# RH025_V2_1.net
KiCad netlist of a schematic drawn in EAGLE
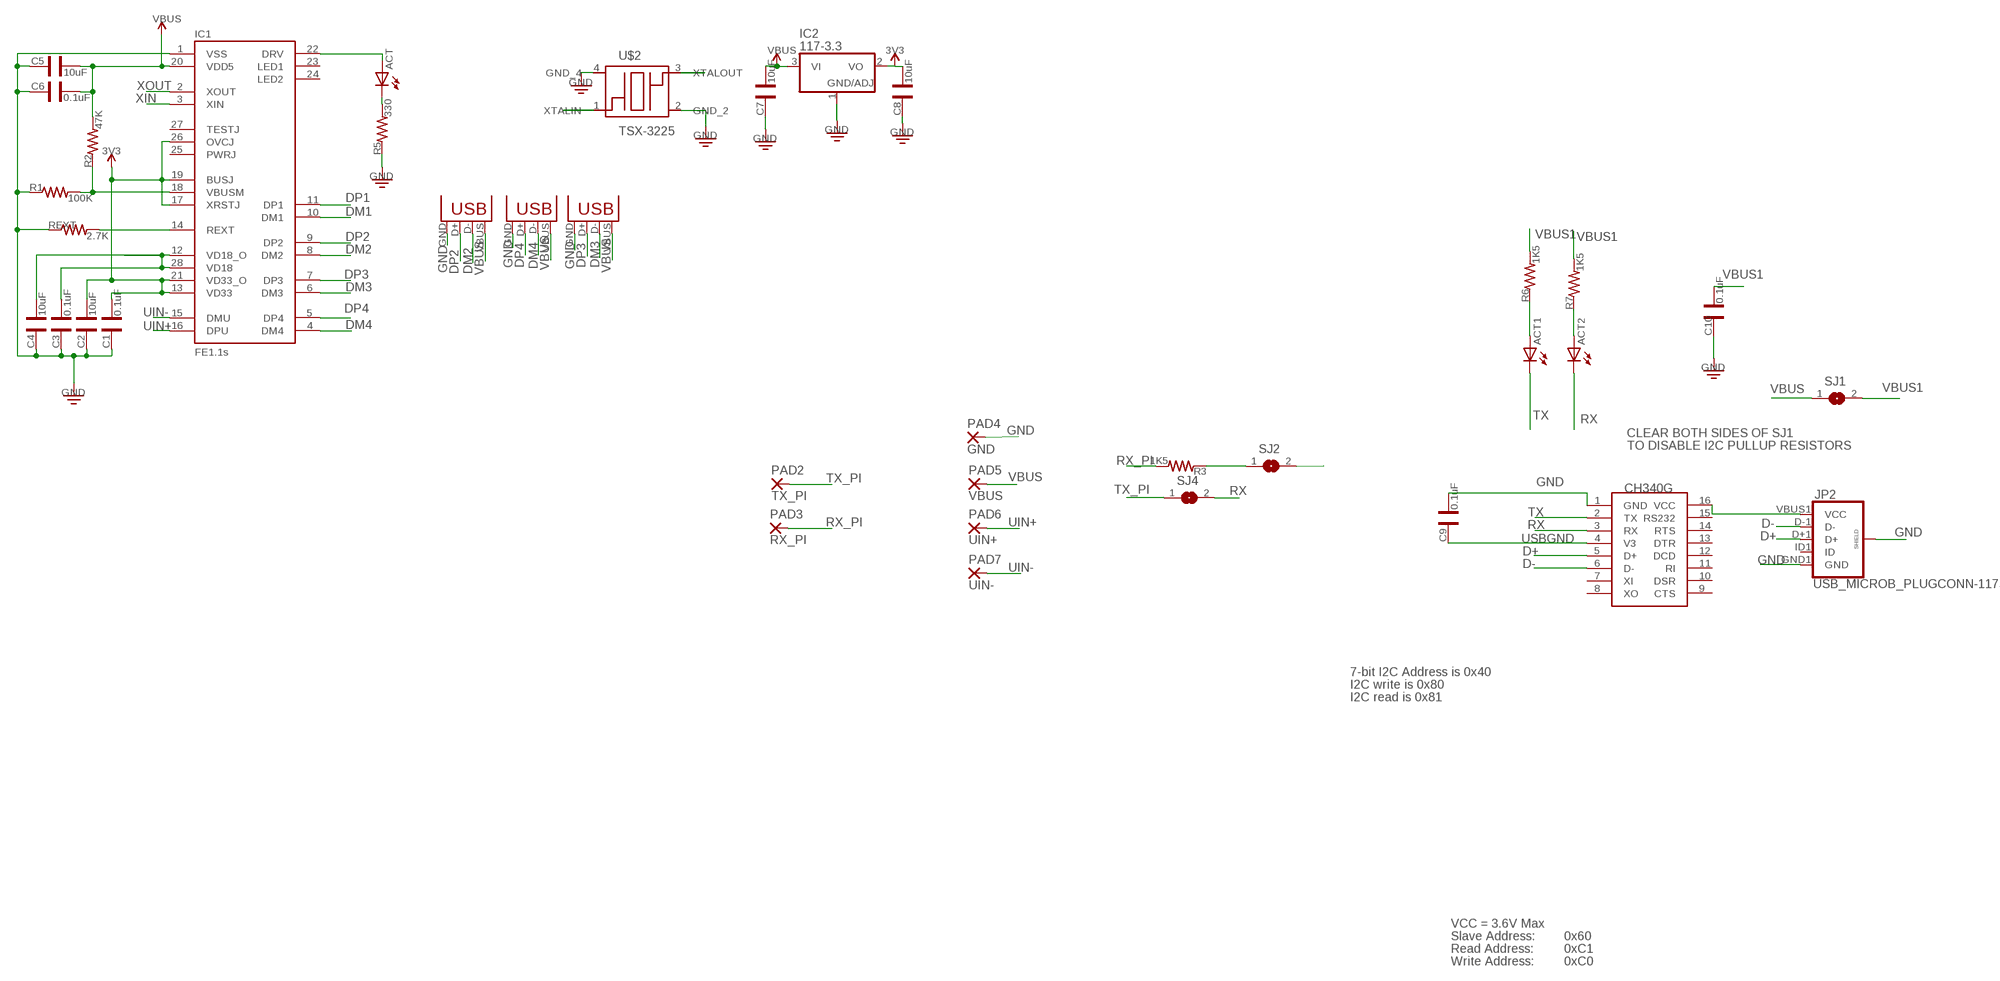
[diagram p0: schematic, sheet 1]

(export (version "E")
  (design (tool "Eeschema 10.0.6"))
  (components
    (comp (ref "ACT")
      (value "LED0805")
      (footprint "eagle-import:LED-0805")
      (libsource (lib "eagle-import") (part "LED0805"))
    )
    (comp (ref "ACT1")
      (value "LED0805")
      (footprint "eagle-import:LED-0805")
      (libsource (lib "eagle-import") (part "LED0805"))
    )
    (comp (ref "ACT2")
      (value "LED0805")
      (footprint "eagle-import:LED-0805")
      (libsource (lib "eagle-import") (part "LED0805"))
    )
    (comp (ref "C1")
      (value "0.1uF")
      (footprint "eagle-import:CAP-0805")
      (libsource (lib "eagle-import") (part "CAP0805"))
    )
    (comp (ref "C2")
      (value "10uF")
      (footprint "eagle-import:CAP-0805")
      (libsource (lib "eagle-import") (part "CAP0805"))
    )
    (comp (ref "C3")
      (value "0.1uF")
      (footprint "eagle-import:CAP-0805")
      (libsource (lib "eagle-import") (part "CAP0805"))
    )
    (comp (ref "C4")
      (value "10uF")
      (footprint "eagle-import:CAP-0805")
      (libsource (lib "eagle-import") (part "CAP0805"))
    )
    (comp (ref "C5")
      (value "10uF")
      (footprint "eagle-import:CAP-0805")
      (libsource (lib "eagle-import") (part "CAP0805"))
    )
    (comp (ref "C6")
      (value "0.1uF")
      (footprint "eagle-import:CAP-0805")
      (libsource (lib "eagle-import") (part "CAP0805"))
    )
    (comp (ref "C7")
      (value "10uF")
      (footprint "eagle-import:CAP-0805")
      (libsource (lib "eagle-import") (part "CAP0805"))
    )
    (comp (ref "C8")
      (value "10uF")
      (footprint "eagle-import:CAP-0805")
      (libsource (lib "eagle-import") (part "CAP0805"))
    )
    (comp (ref "C9")
      (value "0.1uF")
      (footprint "eagle-import:CAP-0805")
      (libsource (lib "eagle-import") (part "CAP0805"))
    )
    (comp (ref "C10")
      (value "0.1uF")
      (footprint "eagle-import:CAP-0805")
      (libsource (lib "eagle-import") (part "CAP0805"))
    )
    (comp (ref "IC1")
      (value "FE1.1S")
      (footprint "eagle-import:FE1.1S_SSOP-28")
      (libsource (lib "eagle-import") (part "FE1.1S"))
    )
    (comp (ref "IC2")
      (value "117-3.3")
      (footprint "eagle-import:SOT223")
      (libsource (lib "eagle-import") (part "1117-3.3EMP"))
    )
    (comp (ref "JP2")
      (value "USB_MICROB_PLUGCONN-11752")
      (footprint "eagle-import:USB-B-MICRO-SMD_V03")
      (libsource (lib "eagle-import") (part "USB_MICROB_PLUGCONN-11752"))
    )
    (comp (ref "PAD2")
      (value "TX_PI")
      (footprint "eagle-import:2,15_1,0")
      (libsource (lib "eagle-import") (part "WIREPAD2,15/1,0"))
    )
    (comp (ref "PAD3")
      (value "RX_PI")
      (footprint "eagle-import:2,15_1,0")
      (libsource (lib "eagle-import") (part "WIREPAD2,15/1,0"))
    )
    (comp (ref "PAD4")
      (value "GND")
      (footprint "eagle-import:2,15_1,0")
      (libsource (lib "eagle-import") (part "WIREPAD2,15/1,0"))
    )
    (comp (ref "PAD5")
      (value "VBUS")
      (footprint "eagle-import:2,15_1,0")
      (libsource (lib "eagle-import") (part "WIREPAD2,15/1,0"))
    )
    (comp (ref "PAD6")
      (value "UIN+")
      (footprint "eagle-import:2,15_1,0")
      (libsource (lib "eagle-import") (part "WIREPAD2,15/1,0"))
    )
    (comp (ref "PAD7")
      (value "UIN-")
      (footprint "eagle-import:2,15_1,0")
      (libsource (lib "eagle-import") (part "WIREPAD2,15/1,0"))
    )
    (comp (ref "R1")
      (value "100K")
      (footprint "eagle-import:RES-0805")
      (libsource (lib "eagle-import") (part "RES0805"))
    )
    (comp (ref "R2")
      (value "47K")
      (footprint "eagle-import:RES-0805")
      (libsource (lib "eagle-import") (part "RES0805"))
    )
    (comp (ref "R3")
      (value "1K5")
      (footprint "eagle-import:RES-0805")
      (libsource (lib "eagle-import") (part "RES0805"))
    )
    (comp (ref "R5")
      (value "330")
      (footprint "eagle-import:RES-0805")
      (libsource (lib "eagle-import") (part "RES0805"))
    )
    (comp (ref "R6")
      (value "1K5")
      (footprint "eagle-import:RES-0805")
      (libsource (lib "eagle-import") (part "RES0805"))
    )
    (comp (ref "R7")
      (value "1K5")
      (footprint "eagle-import:RES-0805")
      (libsource (lib "eagle-import") (part "RES0805"))
    )
    (comp (ref "REXT")
      (value "2.7K")
      (footprint "eagle-import:RES-0805")
      (libsource (lib "eagle-import") (part "RES0805"))
    )
    (comp (ref "SJ1") (value "SJ") (footprint "eagle-import:SJ") (libsource (lib "eagle-import") (part "SJ")))
    (comp (ref "SJ2") (value "SJ") (footprint "eagle-import:SJ") (libsource (lib "eagle-import") (part "SJ")))
    (comp (ref "SJ4") (value "SJ") (footprint "eagle-import:SJ") (libsource (lib "eagle-import") (part "SJ")))
    (comp (ref "U$2")
      (value "TSX-3225")
      (footprint "eagle-import:TSX-3225")
      (libsource (lib "eagle-import") (part "TSX-3225"))
    )
    (comp (ref "U$8")
      (value "CH340C")
      (footprint "eagle-import:SOIC16")
      (libsource (lib "eagle-import") (part "CH340G"))
    )
    (comp (ref "USB2")
      (value "USBA-PTH")
      (footprint "eagle-import:USB-A-F-PTH")
      (libsource (lib "eagle-import") (part "USBA-PTH"))
    )
    (comp (ref "USB3")
      (value "USBA-PTH")
      (footprint "eagle-import:USB-A-F-PTH")
      (libsource (lib "eagle-import") (part "USBA-PTH"))
    )
    (comp (ref "USB4")
      (value "USBA-PTH")
      (footprint "eagle-import:USB-A-F-PTH")
      (libsource (lib "eagle-import") (part "USBA-PTH"))
    )
  )
  (nets
    (net (code "1") (name "/D+") (class "Default")
      (node (ref "JP2") (pin "D+1") (pinfunction "D+_D+1") (pintype "bidirectional"))
      (node (ref "U$8") (pin "5") (pinfunction "D+_5") (pintype "bidirectional"))
    )
    (net (code "2") (name "/D-") (class "Default")
      (node (ref "JP2") (pin "D-1") (pinfunction "D-_D-1") (pintype "bidirectional"))
      (node (ref "U$8") (pin "6") (pinfunction "D-_6") (pintype "bidirectional"))
    )
    (net (code "3") (name "/DM1") (class "Default")
      (node (ref "IC1") (pin "10") (pinfunction "DM1_10") (pintype "bidirectional"))
    )
    (net (code "4") (name "/DM2") (class "Default")
      (node (ref "IC1") (pin "8") (pinfunction "DM2_8") (pintype "bidirectional"))
      (node (ref "USB2") (pin "D-") (pinfunction "D-_D-") (pintype "bidirectional"))
    )
    (net (code "5") (name "/DM3") (class "Default")
      (node (ref "IC1") (pin "6") (pinfunction "DM3_6") (pintype "bidirectional"))
      (node (ref "USB3") (pin "D-") (pinfunction "D-_D-") (pintype "bidirectional"))
    )
    (net (code "6") (name "/DM4") (class "Default")
      (node (ref "IC1") (pin "4") (pinfunction "DM4_4") (pintype "bidirectional"))
      (node (ref "USB4") (pin "D-") (pinfunction "D-_D-") (pintype "bidirectional"))
    )
    (net (code "7") (name "/DP1") (class "Default")
      (node (ref "IC1") (pin "11") (pinfunction "DP1_11") (pintype "bidirectional"))
    )
    (net (code "8") (name "/DP2") (class "Default")
      (node (ref "IC1") (pin "9") (pinfunction "DP2_9") (pintype "bidirectional"))
      (node (ref "USB2") (pin "D+") (pinfunction "D+_D+") (pintype "bidirectional"))
    )
    (net (code "9") (name "/DP3") (class "Default")
      (node (ref "IC1") (pin "7") (pinfunction "DP3_7") (pintype "bidirectional"))
      (node (ref "USB3") (pin "D+") (pinfunction "D+_D+") (pintype "bidirectional"))
    )
    (net (code "10") (name "/DP4") (class "Default")
      (node (ref "IC1") (pin "5") (pinfunction "DP4_5") (pintype "bidirectional"))
      (node (ref "USB4") (pin "D+") (pinfunction "D+_D+") (pintype "bidirectional"))
    )
    (net (code "11") (name "/RX") (class "Default")
      (node (ref "ACT2") (pin "C") (pinfunction "C_C") (pintype "passive"))
      (node (ref "SJ4") (pin "2") (pinfunction "2_2") (pintype "passive"))
      (node (ref "U$8") (pin "3") (pinfunction "RX_3") (pintype "bidirectional"))
    )
    (net (code "12") (name "/RX_PI") (class "Default")
      (node (ref "PAD3") (pin "1") (pinfunction "P_1") (pintype "passive"))
      (node (ref "R3") (pin "2") (pinfunction "2_2") (pintype "passive"))
    )
    (net (code "13") (name "/TX") (class "Default")
      (node (ref "ACT1") (pin "C") (pinfunction "C_C") (pintype "passive"))
      (node (ref "SJ2") (pin "2") (pinfunction "2_2") (pintype "passive"))
      (node (ref "U$8") (pin "2") (pinfunction "TX_2") (pintype "bidirectional"))
    )
    (net (code "14") (name "/TX_PI") (class "Default")
      (node (ref "PAD2") (pin "1") (pinfunction "P_1") (pintype "passive"))
      (node (ref "SJ4") (pin "1") (pinfunction "1_1") (pintype "passive"))
    )
    (net (code "15") (name "/UIN+") (class "Default")
      (node (ref "IC1") (pin "16") (pinfunction "DPU_16") (pintype "bidirectional"))
      (node (ref "PAD6") (pin "1") (pinfunction "P_1") (pintype "passive"))
    )
    (net (code "16") (name "/UIN-") (class "Default")
      (node (ref "IC1") (pin "15") (pinfunction "DMU_15") (pintype "bidirectional"))
      (node (ref "PAD7") (pin "1") (pinfunction "P_1") (pintype "passive"))
    )
    (net (code "17") (name "/USBGND") (class "Default")
      (node (ref "C9") (pin "2") (pinfunction "2_2") (pintype "passive"))
      (node (ref "U$8") (pin "4") (pinfunction "V3_4") (pintype "bidirectional"))
    )
    (net (code "18") (name "/VBUS1") (class "Default")
      (node (ref "C10") (pin "1") (pinfunction "1_1") (pintype "passive"))
      (node (ref "JP2") (pin "VBUS1") (pinfunction "VCC_VBUS1") (pintype "bidirectional"))
      (node (ref "R6") (pin "2") (pinfunction "2_2") (pintype "passive"))
      (node (ref "R7") (pin "2") (pinfunction "2_2") (pintype "passive"))
      (node (ref "SJ1") (pin "2") (pinfunction "2_2") (pintype "passive"))
      (node (ref "U$8") (pin "16") (pinfunction "VCC_16") (pintype "bidirectional"))
    )
    (net (code "19") (name "/XIN") (class "Default")
      (node (ref "IC1") (pin "3") (pinfunction "XIN_3") (pintype "bidirectional"))
      (node (ref "U$2") (pin "1") (pinfunction "XTALIN_1") (pintype "bidirectional"))
    )
    (net (code "20") (name "/XOUT") (class "Default")
      (node (ref "IC1") (pin "2") (pinfunction "XOUT_2") (pintype "bidirectional"))
      (node (ref "U$2") (pin "3") (pinfunction "XTALOUT_3") (pintype "bidirectional"))
    )
    (net (code "21") (name "3V3") (class "Default")
      (node (ref "C1") (pin "1") (pinfunction "1_1") (pintype "passive"))
      (node (ref "C2") (pin "1") (pinfunction "1_1") (pintype "passive"))
      (node (ref "C8") (pin "1") (pinfunction "1_1") (pintype "passive"))
      (node (ref "IC1") (pin "13") (pinfunction "VD33_13") (pintype "bidirectional"))
      (node (ref "IC1") (pin "17") (pinfunction "XRSTJ_17") (pintype "bidirectional"))
      (node (ref "IC1") (pin "19") (pinfunction "BUSJ_19") (pintype "bidirectional"))
      (node (ref "IC1") (pin "21") (pinfunction "VD33_O_21") (pintype "bidirectional"))
      (node (ref "IC1") (pin "26") (pinfunction "OVCJ_26") (pintype "bidirectional"))
      (node (ref "IC2") (pin "2") (pinfunction "VO_2") (pintype "output"))
    )
    (net (code "22") (name "GND") (class "Default")
      (node (ref "C1") (pin "2") (pinfunction "2_2") (pintype "passive"))
      (node (ref "C10") (pin "2") (pinfunction "2_2") (pintype "passive"))
      (node (ref "C2") (pin "2") (pinfunction "2_2") (pintype "passive"))
      (node (ref "C3") (pin "2") (pinfunction "2_2") (pintype "passive"))
      (node (ref "C4") (pin "2") (pinfunction "2_2") (pintype "passive"))
      (node (ref "C5") (pin "2") (pinfunction "2_2") (pintype "passive"))
      (node (ref "C6") (pin "2") (pinfunction "2_2") (pintype "passive"))
      (node (ref "C7") (pin "2") (pinfunction "2_2") (pintype "passive"))
      (node (ref "C8") (pin "2") (pinfunction "2_2") (pintype "passive"))
      (node (ref "C9") (pin "1") (pinfunction "1_1") (pintype "passive"))
      (node (ref "IC1") (pin "1") (pinfunction "VSS_1") (pintype "bidirectional"))
      (node (ref "IC2") (pin "1") (pinfunction "ADJ_1") (pintype "input"))
      (node (ref "JP2") (pin "GND1") (pinfunction "GND_GND1") (pintype "bidirectional"))
      (node (ref "JP2") (pin "SHIELD1") (pinfunction "SHIELD_SHIELD1") (pintype "bidirectional"))
      (node (ref "JP2") (pin "SHIELD2") (pinfunction "SHIELD_SHIELD2") (pintype "bidirectional"))
      (node (ref "JP2") (pin "SHIELD3") (pinfunction "SHIELD_SHIELD3") (pintype "bidirectional"))
      (node (ref "PAD4") (pin "1") (pinfunction "P_1") (pintype "passive"))
      (node (ref "R1") (pin "1") (pinfunction "1_1") (pintype "passive"))
      (node (ref "R5") (pin "1") (pinfunction "1_1") (pintype "passive"))
      (node (ref "REXT") (pin "1") (pinfunction "1_1") (pintype "passive"))
      (node (ref "U$2") (pin "2") (pinfunction "GND_2_2") (pintype "bidirectional"))
      (node (ref "U$2") (pin "4") (pinfunction "GND_4_4") (pintype "bidirectional"))
      (node (ref "U$8") (pin "1") (pinfunction "GND_1") (pintype "bidirectional"))
      (node (ref "USB2") (pin "GND") (pinfunction "GND_GND") (pintype "bidirectional"))
      (node (ref "USB3") (pin "GND") (pinfunction "GND_GND") (pintype "bidirectional"))
      (node (ref "USB4") (pin "GND") (pinfunction "GND_GND") (pintype "bidirectional"))
    )
    (net (code "23") (name "Net-(ACT-PadC)") (class "Default")
      (node (ref "ACT") (pin "C") (pinfunction "C_C") (pintype "passive"))
      (node (ref "R5") (pin "2") (pinfunction "2_2") (pintype "passive"))
    )
    (net (code "24") (name "Net-(ACT1-PadA)") (class "Default")
      (node (ref "ACT1") (pin "A") (pinfunction "A_A") (pintype "passive"))
      (node (ref "R6") (pin "1") (pinfunction "1_1") (pintype "passive"))
    )
    (net (code "25") (name "Net-(ACT2-PadA)") (class "Default")
      (node (ref "ACT2") (pin "A") (pinfunction "A_A") (pintype "passive"))
      (node (ref "R7") (pin "1") (pinfunction "1_1") (pintype "passive"))
    )
    (net (code "26") (name "Net-(IC1-DRV)") (class "Default")
      (node (ref "ACT") (pin "A") (pinfunction "A_A") (pintype "passive"))
      (node (ref "IC1") (pin "22") (pinfunction "DRV_22") (pintype "bidirectional"))
    )
    (net (code "27") (name "Net-(IC1-REXT)") (class "Default")
      (node (ref "IC1") (pin "14") (pinfunction "REXT_14") (pintype "bidirectional"))
      (node (ref "REXT") (pin "2") (pinfunction "2_2") (pintype "passive"))
    )
    (net (code "28") (name "Net-(IC1-VBUSM)") (class "Default")
      (node (ref "IC1") (pin "18") (pinfunction "VBUSM_18") (pintype "bidirectional"))
      (node (ref "R1") (pin "2") (pinfunction "2_2") (pintype "passive"))
      (node (ref "R2") (pin "1") (pinfunction "1_1") (pintype "passive"))
    )
    (net (code "29") (name "Net-(IC1-VD18)") (class "Default")
      (node (ref "C3") (pin "1") (pinfunction "1_1") (pintype "passive"))
      (node (ref "C4") (pin "1") (pinfunction "1_1") (pintype "passive"))
      (node (ref "IC1") (pin "12") (pinfunction "VD18_O_12") (pintype "bidirectional"))
      (node (ref "IC1") (pin "28") (pinfunction "VD18_28") (pintype "bidirectional"))
    )
    (net (code "30") (name "Net-(R3-Pad1)") (class "Default")
      (node (ref "R3") (pin "1") (pinfunction "1_1") (pintype "passive"))
      (node (ref "SJ2") (pin "1") (pinfunction "1_1") (pintype "passive"))
    )
    (net (code "31") (name "VBUS") (class "Default")
      (node (ref "C5") (pin "1") (pinfunction "1_1") (pintype "passive"))
      (node (ref "C6") (pin "1") (pinfunction "1_1") (pintype "passive"))
      (node (ref "C7") (pin "1") (pinfunction "1_1") (pintype "passive"))
      (node (ref "IC1") (pin "20") (pinfunction "VDD5_20") (pintype "bidirectional"))
      (node (ref "IC2") (pin "3") (pinfunction "VI_3") (pintype "input"))
      (node (ref "PAD5") (pin "1") (pinfunction "P_1") (pintype "passive"))
      (node (ref "R2") (pin "2") (pinfunction "2_2") (pintype "passive"))
      (node (ref "SJ1") (pin "1") (pinfunction "1_1") (pintype "passive"))
      (node (ref "USB2") (pin "VBUS") (pinfunction "VBUS_VBUS") (pintype "bidirectional"))
      (node (ref "USB3") (pin "VBUS") (pinfunction "VBUS_VBUS") (pintype "bidirectional"))
      (node (ref "USB4") (pin "VBUS") (pinfunction "VBUS_VBUS") (pintype "bidirectional"))
    )
    (net (code "32") (name "unconnected-(IC1-LED1-Pad23)") (class "Default")
      (node (ref "IC1") (pin "23") (pinfunction "LED1_23") (pintype "bidirectional"))
    )
    (net (code "33") (name "unconnected-(IC1-LED2-Pad24)") (class "Default")
      (node (ref "IC1") (pin "24") (pinfunction "LED2_24") (pintype "bidirectional"))
    )
    (net (code "34") (name "unconnected-(IC1-PWRJ-Pad25)") (class "Default")
      (node (ref "IC1") (pin "25") (pinfunction "PWRJ_25") (pintype "bidirectional"))
    )
    (net (code "35") (name "unconnected-(IC1-TESTJ-Pad27)") (class "Default")
      (node (ref "IC1") (pin "27") (pinfunction "TESTJ_27") (pintype "bidirectional"))
    )
    (net (code "36") (name "unconnected-(JP2-ID-PadID1)") (class "Default")
      (node (ref "JP2") (pin "ID1") (pinfunction "ID_ID1") (pintype "bidirectional"))
    )
    (net (code "37") (name "unconnected-(U$8-CTS-Pad9)") (class "Default")
      (node (ref "U$8") (pin "9") (pinfunction "CTS_9") (pintype "bidirectional"))
    )
    (net (code "38") (name "unconnected-(U$8-DCD-Pad12)") (class "Default")
      (node (ref "U$8") (pin "12") (pinfunction "DCD_12") (pintype "bidirectional"))
    )
    (net (code "39") (name "unconnected-(U$8-DSR-Pad10)") (class "Default")
      (node (ref "U$8") (pin "10") (pinfunction "DSR_10") (pintype "bidirectional"))
    )
    (net (code "40") (name "unconnected-(U$8-DTR-Pad13)") (class "Default")
      (node (ref "U$8") (pin "13") (pinfunction "DTR_13") (pintype "bidirectional"))
    )
    (net (code "41") (name "unconnected-(U$8-RI-Pad11)") (class "Default")
      (node (ref "U$8") (pin "11") (pinfunction "RI_11") (pintype "bidirectional"))
    )
    (net (code "42") (name "unconnected-(U$8-RS232-Pad15)") (class "Default")
      (node (ref "U$8") (pin "15") (pinfunction "RS232_15") (pintype "bidirectional"))
    )
    (net (code "43") (name "unconnected-(U$8-RTS-Pad14)") (class "Default")
      (node (ref "U$8") (pin "14") (pinfunction "RTS_14") (pintype "bidirectional"))
    )
    (net (code "44") (name "unconnected-(U$8-XI-Pad7)") (class "Default")
      (node (ref "U$8") (pin "7") (pinfunction "XI_7") (pintype "bidirectional"))
    )
    (net (code "45") (name "unconnected-(U$8-XO-Pad8)") (class "Default")
      (node (ref "U$8") (pin "8") (pinfunction "XO_8") (pintype "bidirectional"))
    )
  )
)
